# 4-20_mA_Circuit.net
KiCad netlist of a schematic drawn in EAGLE
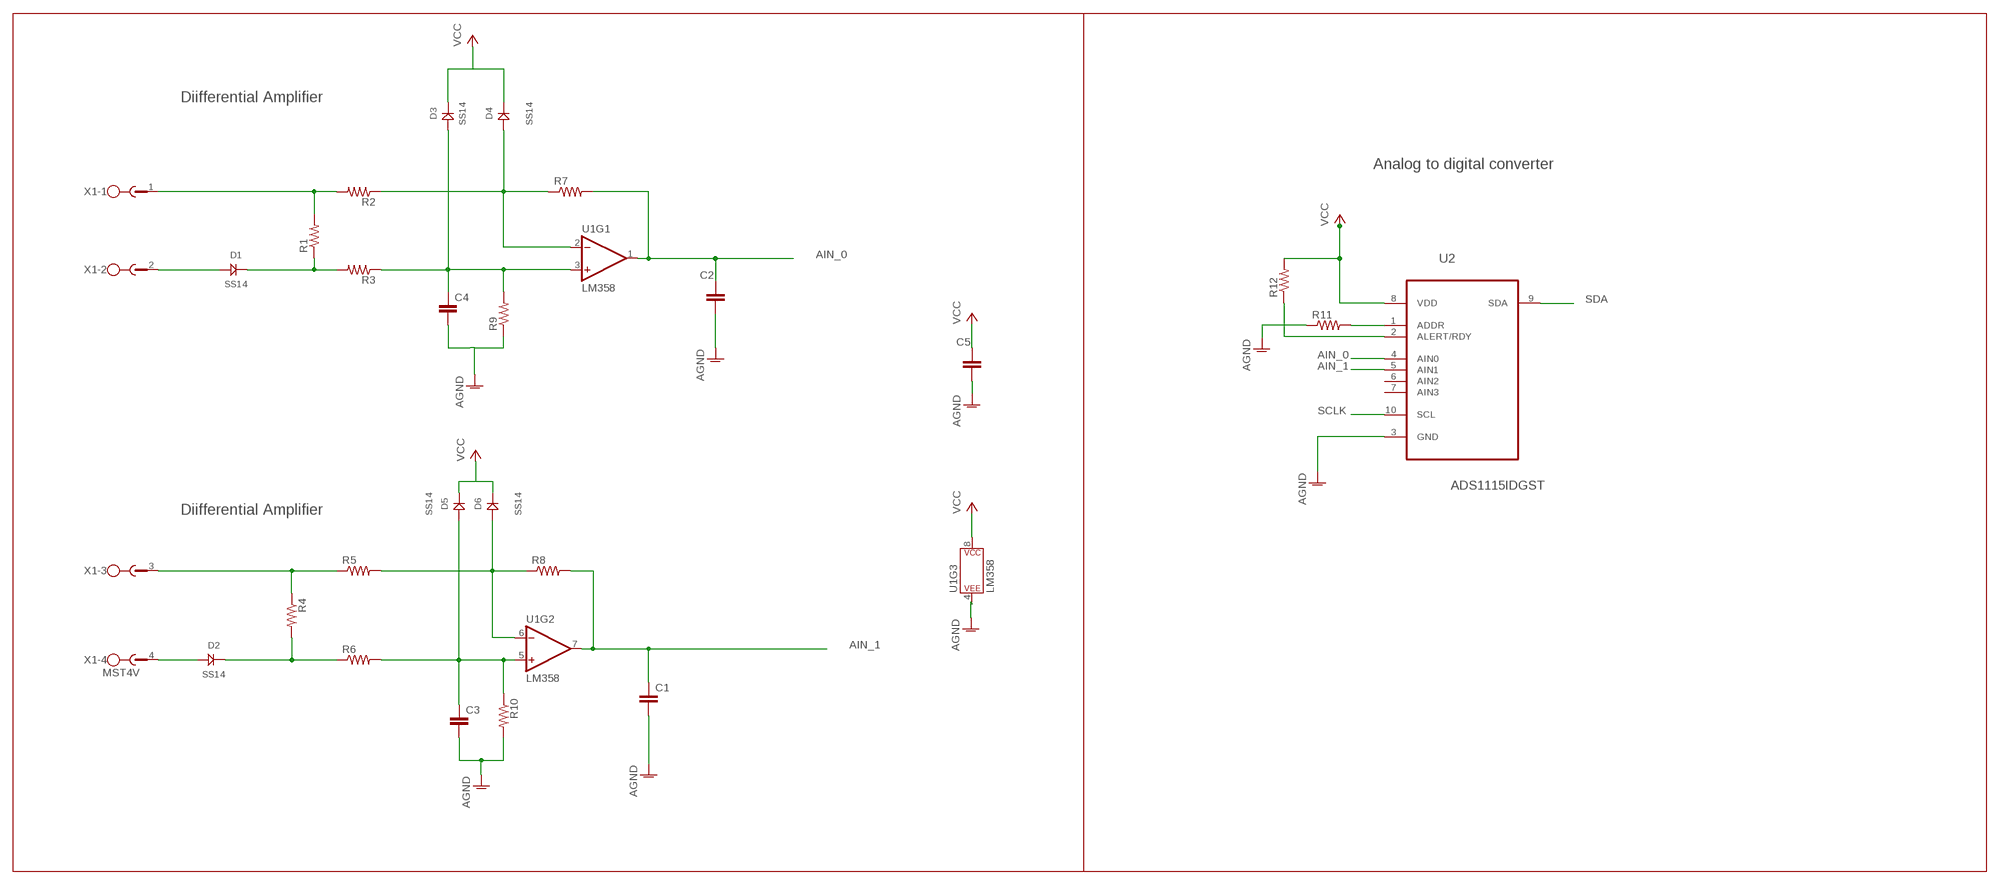
[diagram p0: schematic, sheet 1]

(export (version "E")
  (design (tool "Eeschema 10.0.6"))
  (components
    (comp (ref "C1")
      (value "C-EUC0805")
      (footprint "eagle-import:C0805")
      (libsource (lib "eagle-import") (part "C-EUC0805"))
    )
    (comp (ref "C2")
      (value "C-EUC0805")
      (footprint "eagle-import:C0805")
      (libsource (lib "eagle-import") (part "C-EUC0805"))
    )
    (comp (ref "C3")
      (value "C-EUC0805")
      (footprint "eagle-import:C0805")
      (libsource (lib "eagle-import") (part "C-EUC0805"))
    )
    (comp (ref "C4")
      (value "C-EUC0805")
      (footprint "eagle-import:C0805")
      (libsource (lib "eagle-import") (part "C-EUC0805"))
    )
    (comp (ref "C5")
      (value "C-EUC0805")
      (footprint "eagle-import:C0805")
      (libsource (lib "eagle-import") (part "C-EUC0805"))
    )
    (comp (ref "D1")
      (value "SS14")
      (footprint "eagle-import:DO214")
      (fields (field (name "MF") "ON Semiconductor"))
      (libsource (lib "eagle-import") (part "SS14"))
    )
    (comp (ref "D2")
      (value "SS14")
      (footprint "eagle-import:DO214")
      (fields (field (name "MF") "ON Semiconductor"))
      (libsource (lib "eagle-import") (part "SS14"))
    )
    (comp (ref "D3")
      (value "SS14")
      (footprint "eagle-import:DO214")
      (fields (field (name "MF") "ON Semiconductor"))
      (libsource (lib "eagle-import") (part "SS14"))
    )
    (comp (ref "D4")
      (value "SS14")
      (footprint "eagle-import:DO214")
      (fields (field (name "MF") "ON Semiconductor"))
      (libsource (lib "eagle-import") (part "SS14"))
    )
    (comp (ref "D5")
      (value "SS14")
      (footprint "eagle-import:DO214")
      (fields (field (name "MF") "ON Semiconductor"))
      (libsource (lib "eagle-import") (part "SS14"))
    )
    (comp (ref "D6")
      (value "SS14")
      (footprint "eagle-import:DO214")
      (fields (field (name "MF") "ON Semiconductor"))
      (libsource (lib "eagle-import") (part "SS14"))
    )
    (comp (ref "R1")
      (value "R-US_R0805")
      (footprint "eagle-import:R0805")
      (libsource (lib "eagle-import") (part "R-US_R0805"))
    )
    (comp (ref "R2")
      (value "R-US_R0805")
      (footprint "eagle-import:R0805")
      (libsource (lib "eagle-import") (part "R-US_R0805"))
    )
    (comp (ref "R3")
      (value "R-US_R0805")
      (footprint "eagle-import:R0805")
      (libsource (lib "eagle-import") (part "R-US_R0805"))
    )
    (comp (ref "R4")
      (value "R-US_R0805")
      (footprint "eagle-import:R0805")
      (libsource (lib "eagle-import") (part "R-US_R0805"))
    )
    (comp (ref "R5")
      (value "R-US_R0805")
      (footprint "eagle-import:R0805")
      (libsource (lib "eagle-import") (part "R-US_R0805"))
    )
    (comp (ref "R6")
      (value "R-US_R0805")
      (footprint "eagle-import:R0805")
      (libsource (lib "eagle-import") (part "R-US_R0805"))
    )
    (comp (ref "R7")
      (value "R-US_R0805")
      (footprint "eagle-import:R0805")
      (libsource (lib "eagle-import") (part "R-US_R0805"))
    )
    (comp (ref "R8")
      (value "R-US_R0805")
      (footprint "eagle-import:R0805")
      (libsource (lib "eagle-import") (part "R-US_R0805"))
    )
    (comp (ref "R9")
      (value "R-US_R0805")
      (footprint "eagle-import:R0805")
      (libsource (lib "eagle-import") (part "R-US_R0805"))
    )
    (comp (ref "R10")
      (value "R-US_R0805")
      (footprint "eagle-import:R0805")
      (libsource (lib "eagle-import") (part "R-US_R0805"))
    )
    (comp (ref "R11")
      (value "R-US_R0805")
      (footprint "eagle-import:R0805")
      (libsource (lib "eagle-import") (part "R-US_R0805"))
    )
    (comp (ref "R12")
      (value "R-US_R0805")
      (footprint "eagle-import:R0805")
      (libsource (lib "eagle-import") (part "R-US_R0805"))
    )
    (comp (ref "U1")
      (value "LM358")
      (footprint "eagle-import:DIP08")
      (libsource (lib "eagle-import") (part "LM358"))
    )
    (comp (ref "U2")
      (value "ADS1115IDGST")
      (footprint "eagle-import:SOP50P490X110-10N")
      (fields (field (name "MF") "Texas Instruments"))
      (libsource (lib "eagle-import") (part "ADS1115IDGST"))
    )
    (comp (ref "X1")
      (value "MST4V")
      (footprint "eagle-import:MSTBV4")
      (libsource (lib "eagle-import") (part "MST4V"))
    )
  )
  (nets
    (net (code "1") (name "/AIN_0") (class "Default")
      (node (ref "C2") (pin "1") (pinfunction "1_1") (pintype "passive"))
      (node (ref "R7") (pin "2") (pinfunction "2_2") (pintype "passive"))
      (node (ref "U1") (pin "1") (pinfunction "OUT_1") (pintype "output"))
      (node (ref "U2") (pin "4") (pinfunction "AIN0_4") (pintype "input"))
    )
    (net (code "2") (name "/AIN_1") (class "Default")
      (node (ref "C1") (pin "1") (pinfunction "1_1") (pintype "passive"))
      (node (ref "R8") (pin "2") (pinfunction "2_2") (pintype "passive"))
      (node (ref "U1") (pin "7") (pinfunction "OUT_7") (pintype "output"))
      (node (ref "U2") (pin "5") (pinfunction "AIN1_5") (pintype "input"))
    )
    (net (code "3") (name "/SCLK") (class "Default")
      (node (ref "U2") (pin "10") (pinfunction "SCL_10") (pintype "input"))
    )
    (net (code "4") (name "/SDA") (class "Default")
      (node (ref "U2") (pin "9") (pinfunction "SDA_9") (pintype "bidirectional"))
    )
    (net (code "5") (name "AGND") (class "Default")
      (node (ref "C1") (pin "2") (pinfunction "2_2") (pintype "passive"))
      (node (ref "C2") (pin "2") (pinfunction "2_2") (pintype "passive"))
      (node (ref "C3") (pin "2") (pinfunction "2_2") (pintype "passive"))
      (node (ref "C4") (pin "2") (pinfunction "2_2") (pintype "passive"))
      (node (ref "C5") (pin "2") (pinfunction "2_2") (pintype "passive"))
      (node (ref "R10") (pin "2") (pinfunction "2_2") (pintype "passive"))
      (node (ref "R11") (pin "1") (pinfunction "1_1") (pintype "passive"))
      (node (ref "R9") (pin "1") (pinfunction "1_1") (pintype "passive"))
      (node (ref "U1") (pin "4") (pinfunction "P$V-_4") (pintype "bidirectional"))
      (node (ref "U2") (pin "3") (pinfunction "GND_3") (pintype "passive"))
    )
    (net (code "6") (name "Net-(D1-KATHODE)") (class "Default")
      (node (ref "D1") (pin "CATHODE") (pinfunction "KATHODE_CATHODE") (pintype "bidirectional"))
      (node (ref "R1") (pin "1") (pinfunction "1_1") (pintype "passive"))
      (node (ref "R3") (pin "2") (pinfunction "2_2") (pintype "passive"))
    )
    (net (code "7") (name "Net-(D2-KATHODE)") (class "Default")
      (node (ref "D2") (pin "CATHODE") (pinfunction "KATHODE_CATHODE") (pintype "bidirectional"))
      (node (ref "R4") (pin "2") (pinfunction "2_2") (pintype "passive"))
      (node (ref "R6") (pin "1") (pinfunction "1_1") (pintype "passive"))
    )
    (net (code "8") (name "Net-(R1-Pad2)") (class "Default")
      (node (ref "R1") (pin "2") (pinfunction "2_2") (pintype "passive"))
      (node (ref "R2") (pin "2") (pinfunction "2_2") (pintype "passive"))
      (node (ref "X1") (pin "1") (pinfunction "1_1") (pintype "passive"))
    )
    (net (code "9") (name "Net-(U1A-+IN)") (class "Default")
      (node (ref "C4") (pin "1") (pinfunction "1_1") (pintype "passive"))
      (node (ref "D3") (pin "ANODE") (pinfunction "ANODE_ANODE") (pintype "bidirectional"))
      (node (ref "R3") (pin "1") (pinfunction "1_1") (pintype "passive"))
      (node (ref "R9") (pin "2") (pinfunction "2_2") (pintype "passive"))
      (node (ref "U1") (pin "3") (pinfunction "+IN_3") (pintype "input"))
    )
    (net (code "10") (name "Net-(U1A--IN)") (class "Default")
      (node (ref "D4") (pin "ANODE") (pinfunction "ANODE_ANODE") (pintype "bidirectional"))
      (node (ref "R2") (pin "1") (pinfunction "1_1") (pintype "passive"))
      (node (ref "R7") (pin "1") (pinfunction "1_1") (pintype "passive"))
      (node (ref "U1") (pin "2") (pinfunction "-IN_2") (pintype "input"))
    )
    (net (code "11") (name "Net-(U1B-+IN)") (class "Default")
      (node (ref "C3") (pin "1") (pinfunction "1_1") (pintype "passive"))
      (node (ref "D5") (pin "ANODE") (pinfunction "ANODE_ANODE") (pintype "bidirectional"))
      (node (ref "R10") (pin "1") (pinfunction "1_1") (pintype "passive"))
      (node (ref "R6") (pin "2") (pinfunction "2_2") (pintype "passive"))
      (node (ref "U1") (pin "5") (pinfunction "+IN_5") (pintype "input"))
    )
    (net (code "12") (name "Net-(U1B--IN)") (class "Default")
      (node (ref "D6") (pin "ANODE") (pinfunction "ANODE_ANODE") (pintype "bidirectional"))
      (node (ref "R5") (pin "2") (pinfunction "2_2") (pintype "passive"))
      (node (ref "R8") (pin "1") (pinfunction "1_1") (pintype "passive"))
      (node (ref "U1") (pin "6") (pinfunction "-IN_6") (pintype "input"))
    )
    (net (code "13") (name "Net-(U2-ADDR)") (class "Default")
      (node (ref "R11") (pin "2") (pinfunction "2_2") (pintype "passive"))
      (node (ref "U2") (pin "1") (pinfunction "ADDR_1") (pintype "input"))
    )
    (net (code "14") (name "Net-(U2-ALERT{slash}RDY)") (class "Default")
      (node (ref "R12") (pin "1") (pinfunction "1_1") (pintype "passive"))
      (node (ref "U2") (pin "2") (pinfunction "ALERT/RDY_2") (pintype "input"))
    )
    (net (code "15") (name "Net-(X1B-1)") (class "Default")
      (node (ref "D1") (pin "ANODE") (pinfunction "ANODE_ANODE") (pintype "bidirectional"))
      (node (ref "X1") (pin "2") (pinfunction "1_2") (pintype "passive"))
    )
    (net (code "16") (name "Net-(X1C-1)") (class "Default")
      (node (ref "R4") (pin "1") (pinfunction "1_1") (pintype "passive"))
      (node (ref "R5") (pin "1") (pinfunction "1_1") (pintype "passive"))
      (node (ref "X1") (pin "3") (pinfunction "1_3") (pintype "passive"))
    )
    (net (code "17") (name "Net-(X1D-1)") (class "Default")
      (node (ref "D2") (pin "ANODE") (pinfunction "ANODE_ANODE") (pintype "bidirectional"))
      (node (ref "X1") (pin "4") (pinfunction "1_4") (pintype "passive"))
    )
    (net (code "18") (name "VCC") (class "Default")
      (node (ref "C5") (pin "1") (pinfunction "1_1") (pintype "passive"))
      (node (ref "D3") (pin "CATHODE") (pinfunction "KATHODE_CATHODE") (pintype "bidirectional"))
      (node (ref "D4") (pin "CATHODE") (pinfunction "KATHODE_CATHODE") (pintype "bidirectional"))
      (node (ref "D5") (pin "CATHODE") (pinfunction "KATHODE_CATHODE") (pintype "bidirectional"))
      (node (ref "D6") (pin "CATHODE") (pinfunction "KATHODE_CATHODE") (pintype "bidirectional"))
      (node (ref "R12") (pin "2") (pinfunction "2_2") (pintype "passive"))
      (node (ref "U1") (pin "8") (pinfunction "P$V+_8") (pintype "bidirectional"))
      (node (ref "U2") (pin "8") (pinfunction "VDD_8") (pintype "power_in"))
    )
    (net (code "19") (name "unconnected-(U2-AIN2-Pad6)") (class "Default")
      (node (ref "U2") (pin "6") (pinfunction "AIN2_6") (pintype "input"))
    )
    (net (code "20") (name "unconnected-(U2-AIN3-Pad7)") (class "Default")
      (node (ref "U2") (pin "7") (pinfunction "AIN3_7") (pintype "input"))
    )
  )
)
